# laugh_cry.net
KiCad netlist of a schematic drawn in EAGLE
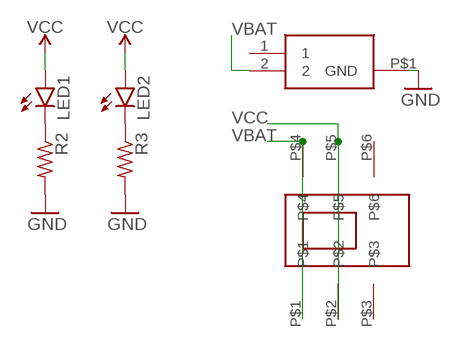
[diagram p0: schematic, sheet 1]

(export (version "E")
  (design (tool "Eeschema 10.0.6"))
  (components
    (comp (ref "LED1")
      (value "LEDCHIP-LED0805")
      (footprint "eagle-import:CHIP-LED0805")
      (libsource (lib "eagle-import") (part "LEDCHIP-LED0805"))
    )
    (comp (ref "LED2")
      (value "LEDCHIP-LED0805")
      (footprint "eagle-import:CHIP-LED0805")
      (libsource (lib "eagle-import") (part "LEDCHIP-LED0805"))
    )
    (comp (ref "R2")
      (value "R-US_R0603")
      (footprint "eagle-import:R0603")
      (libsource (lib "eagle-import") (part "R-US_R0603"))
    )
    (comp (ref "R3")
      (value "R-US_R0603")
      (footprint "eagle-import:R0603")
      (libsource (lib "eagle-import") (part "R-US_R0603"))
    )
    (comp (ref "U$1")
      (value "CL-SB-22A-02T-SLIDE-SWITCH-TUCKED-PADS")
      (footprint "eagle-import:CL-SB-22A-02T-DPDT-COMPACT-SWITCH")
      (libsource (lib "eagle-import") (part "CL-SB-22A-02T-SLIDE-SWITCH-TUCKED-PADS"))
    )
    (comp (ref "VBAT")
      (value "BAT-HLD-012-SMT")
      (footprint "eagle-import:BATHLD012SMT")
      (fields (field (name "MOUSER_PART_NUMBER") "712-BAT-HLD-012-SMT"))
      (libsource (lib "eagle-import") (part "BAT-HLD-012-SMT"))
    )
  )
  (nets
    (net (code "1") (name "/VBAT") (class "Default")
      (node (ref "U$1") (pin "P$1") (pinfunction "P$1_P$1") (pintype "bidirectional"))
      (node (ref "U$1") (pin "P$4") (pinfunction "P$4_P$4") (pintype "bidirectional"))
      (node (ref "VBAT") (pin "2") (pinfunction "2_2") (pintype "bidirectional"))
    )
    (net (code "2") (name "GND") (class "Default")
      (node (ref "R2") (pin "2") (pinfunction "2_2") (pintype "passive"))
      (node (ref "R3") (pin "2") (pinfunction "2_2") (pintype "passive"))
      (node (ref "VBAT") (pin "P$1") (pinfunction "GND_P$1") (pintype "bidirectional"))
    )
    (net (code "3") (name "Net-(LED1-PadC)") (class "Default")
      (node (ref "LED1") (pin "C") (pinfunction "C_C") (pintype "passive"))
      (node (ref "R2") (pin "1") (pinfunction "1_1") (pintype "passive"))
    )
    (net (code "4") (name "Net-(LED2-PadC)") (class "Default")
      (node (ref "LED2") (pin "C") (pinfunction "C_C") (pintype "passive"))
      (node (ref "R3") (pin "1") (pinfunction "1_1") (pintype "passive"))
    )
    (net (code "5") (name "VCC") (class "Default")
      (node (ref "LED1") (pin "A") (pinfunction "A_A") (pintype "passive"))
      (node (ref "LED2") (pin "A") (pinfunction "A_A") (pintype "passive"))
      (node (ref "U$1") (pin "P$2") (pinfunction "P$2_P$2") (pintype "bidirectional"))
      (node (ref "U$1") (pin "P$5") (pinfunction "P$5_P$5") (pintype "bidirectional"))
    )
    (net (code "6") (name "unconnected-(U$1-PadP$3)") (class "Default")
      (node (ref "U$1") (pin "P$3") (pinfunction "P$3_P$3") (pintype "bidirectional"))
    )
    (net (code "7") (name "unconnected-(U$1-PadP$6)") (class "Default")
      (node (ref "U$1") (pin "P$6") (pinfunction "P$6_P$6") (pintype "bidirectional"))
    )
    (net (code "8") (name "unconnected-(VBAT-Pad1)") (class "Default")
      (node (ref "VBAT") (pin "1") (pinfunction "1_1") (pintype "bidirectional"))
    )
  )
)
